# untitled.net
KiCad netlist of a schematic drawn in EAGLE
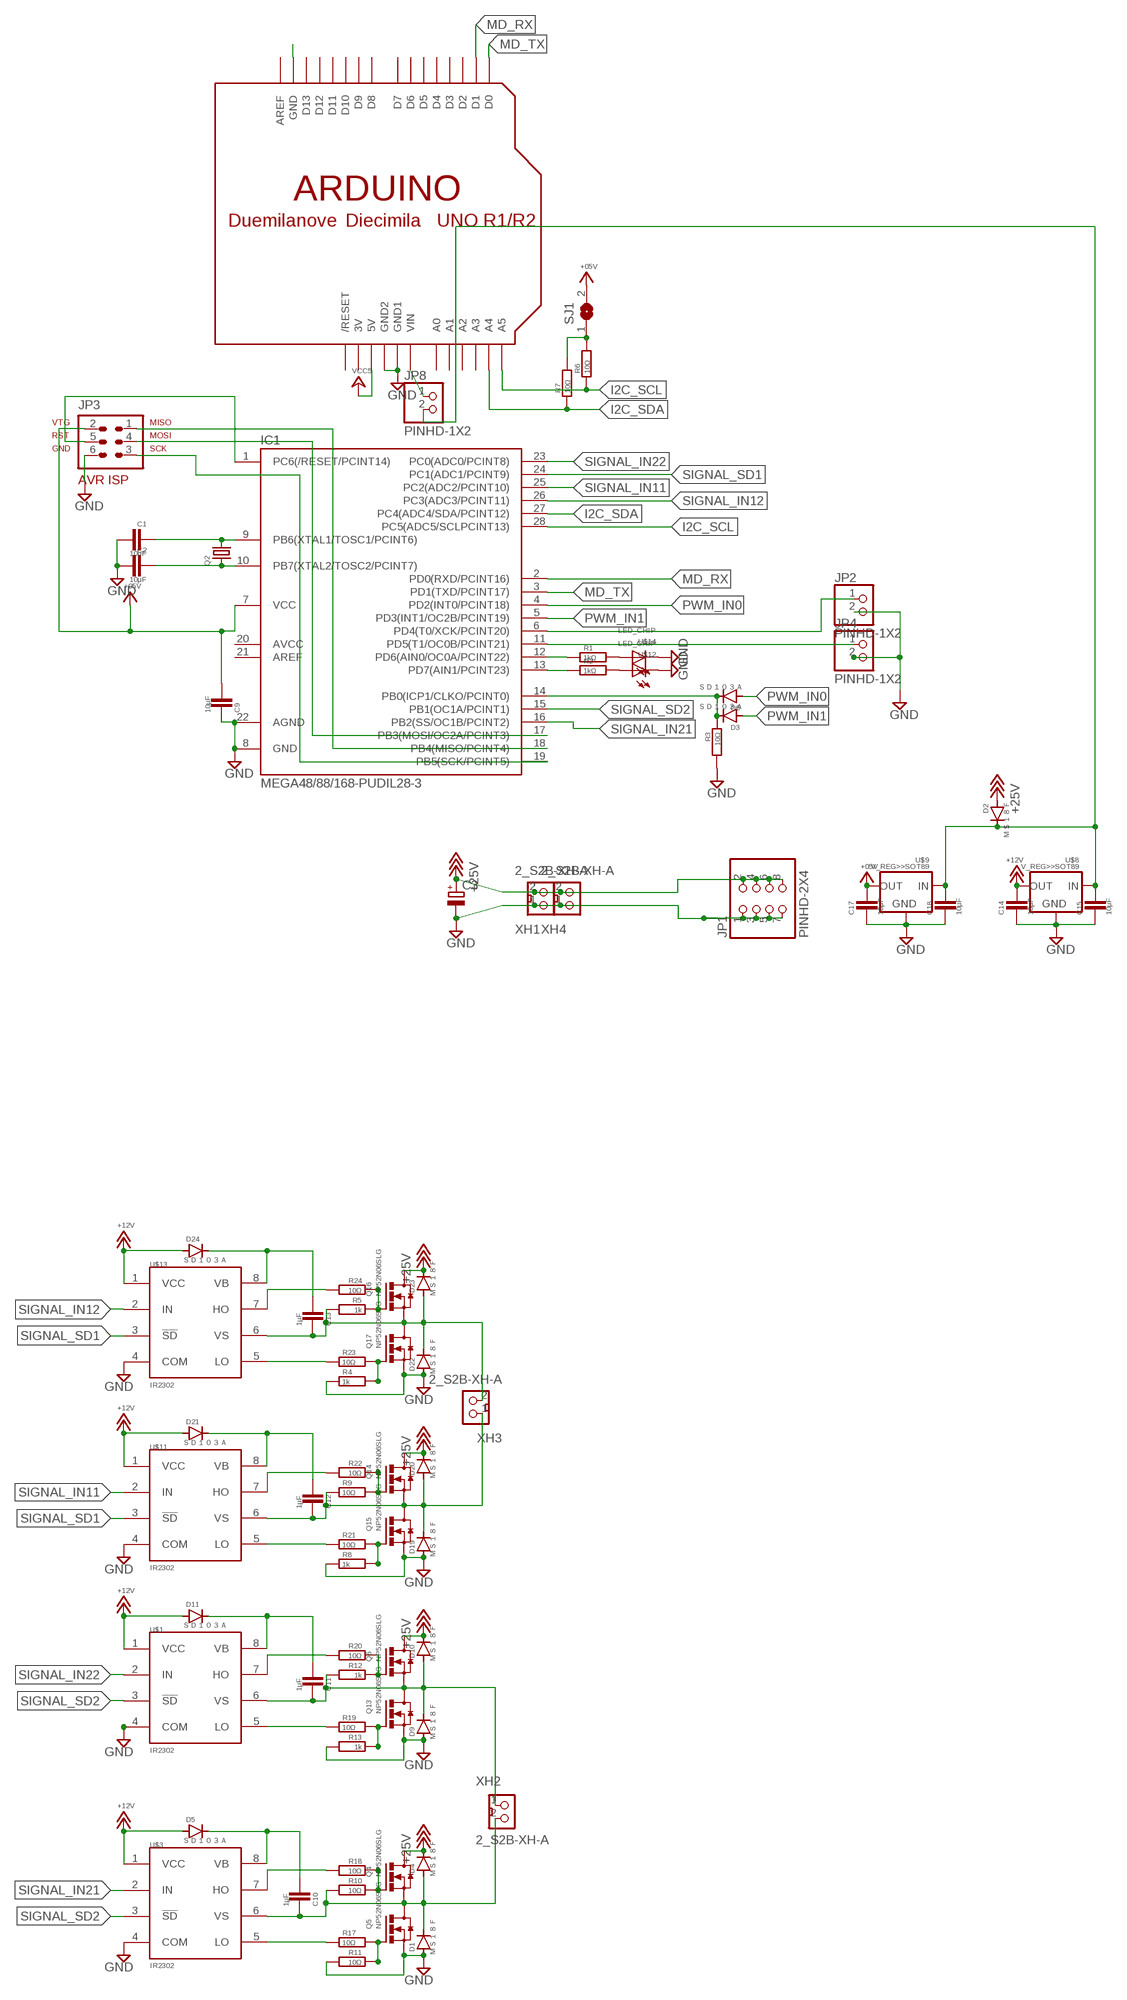
[diagram p0: schematic, sheet 1]

(export (version "E")
  (design (tool "Eeschema 10.0.6"))
  (components
    (comp (ref "C1")
      (value "10μF")
      (footprint "eagle-import:2012")
      (libsource (lib "eagle-import") (part "CAPACITOR{gt}{gt}2012"))
    )
    (comp (ref "C2")
      (value "10μF")
      (footprint "eagle-import:2012")
      (libsource (lib "eagle-import") (part "CAPACITOR{gt}{gt}2012"))
    )
    (comp (ref "C3")
      (value "CPOL-EUUD-6,3X8,8")
      (footprint "eagle-import:UD-6,3X5,8_NICHICON")
      (libsource (lib "eagle-import") (part "CPOL-EUUD-6,3X8,8"))
    )
    (comp (ref "C9")
      (value "10μF")
      (footprint "eagle-import:2012")
      (libsource (lib "eagle-import") (part "CAPACITOR{gt}{gt}2012"))
    )
    (comp (ref "C10")
      (value "1μF")
      (footprint "eagle-import:2012")
      (libsource (lib "eagle-import") (part "CAPACITOR{gt}{gt}2012"))
    )
    (comp (ref "C11")
      (value "1μF")
      (footprint "eagle-import:2012")
      (libsource (lib "eagle-import") (part "CAPACITOR{gt}{gt}2012"))
    )
    (comp (ref "C12")
      (value "1μF")
      (footprint "eagle-import:2012")
      (libsource (lib "eagle-import") (part "CAPACITOR{gt}{gt}2012"))
    )
    (comp (ref "C13")
      (value "1μF")
      (footprint "eagle-import:2012")
      (libsource (lib "eagle-import") (part "CAPACITOR{gt}{gt}2012"))
    )
    (comp (ref "C14")
      (value "10μF")
      (footprint "eagle-import:2012")
      (libsource (lib "eagle-import") (part "CAPACITOR{gt}{gt}2012"))
    )
    (comp (ref "C15")
      (value "10μF")
      (footprint "eagle-import:2012")
      (libsource (lib "eagle-import") (part "CAPACITOR{gt}{gt}2012"))
    )
    (comp (ref "C17")
      (value "10μF")
      (footprint "eagle-import:2012")
      (libsource (lib "eagle-import") (part "CAPACITOR{gt}{gt}2012"))
    )
    (comp (ref "C18")
      (value "10μF")
      (footprint "eagle-import:2012")
      (libsource (lib "eagle-import") (part "CAPACITOR{gt}{gt}2012"))
    )
    (comp (ref "D1")
      (value "ＭＳ１８Ｆ")
      (footprint "eagle-import:MS18F")
      (libsource (lib "eagle-import") (part "DIODE{gt}{gt}MS18F"))
    )
    (comp (ref "D2")
      (value "ＭＳ１８Ｆ")
      (footprint "eagle-import:MS18F")
      (libsource (lib "eagle-import") (part "DIODE{gt}{gt}MS18F"))
    )
    (comp (ref "D3")
      (value "ＳＤ１０３Ａ")
      (footprint "eagle-import:SOD123")
      (libsource (lib "eagle-import") (part "DIODE{gt}{gt}SOD123"))
    )
    (comp (ref "D4")
      (value "ＭＳ１８Ｆ")
      (footprint "eagle-import:MS18F")
      (libsource (lib "eagle-import") (part "DIODE{gt}{gt}MS18F"))
    )
    (comp (ref "D5")
      (value "ＳＤ１０３Ａ")
      (footprint "eagle-import:SOD123")
      (libsource (lib "eagle-import") (part "DIODE{gt}{gt}SOD123"))
    )
    (comp (ref "D6")
      (value "ＳＤ１０３Ａ")
      (footprint "eagle-import:SOD123")
      (libsource (lib "eagle-import") (part "DIODE{gt}{gt}SOD123"))
    )
    (comp (ref "D9")
      (value "ＭＳ１８Ｆ")
      (footprint "eagle-import:MS18F")
      (libsource (lib "eagle-import") (part "DIODE{gt}{gt}MS18F"))
    )
    (comp (ref "D10")
      (value "ＭＳ１８Ｆ")
      (footprint "eagle-import:MS18F")
      (libsource (lib "eagle-import") (part "DIODE{gt}{gt}MS18F"))
    )
    (comp (ref "D11")
      (value "ＳＤ１０３Ａ")
      (footprint "eagle-import:SOD123")
      (libsource (lib "eagle-import") (part "DIODE{gt}{gt}SOD123"))
    )
    (comp (ref "D19")
      (value "ＭＳ１８Ｆ")
      (footprint "eagle-import:MS18F")
      (libsource (lib "eagle-import") (part "DIODE{gt}{gt}MS18F"))
    )
    (comp (ref "D20")
      (value "ＭＳ１８Ｆ")
      (footprint "eagle-import:MS18F")
      (libsource (lib "eagle-import") (part "DIODE{gt}{gt}MS18F"))
    )
    (comp (ref "D21")
      (value "ＳＤ１０３Ａ")
      (footprint "eagle-import:SOD123")
      (libsource (lib "eagle-import") (part "DIODE{gt}{gt}SOD123"))
    )
    (comp (ref "D22")
      (value "ＭＳ１８Ｆ")
      (footprint "eagle-import:MS18F")
      (libsource (lib "eagle-import") (part "DIODE{gt}{gt}MS18F"))
    )
    (comp (ref "D23")
      (value "ＭＳ１８Ｆ")
      (footprint "eagle-import:MS18F")
      (libsource (lib "eagle-import") (part "DIODE{gt}{gt}MS18F"))
    )
    (comp (ref "D24")
      (value "ＳＤ１０３Ａ")
      (footprint "eagle-import:SOD123")
      (libsource (lib "eagle-import") (part "DIODE{gt}{gt}SOD123"))
    )
    (comp (ref "IC1")
      (value "MEGA48/88/168-PUDIL28-3")
      (footprint "eagle-import:DIL28-3")
      (libsource (lib "eagle-import") (part "MEGA48/88/168-PUDIL28-3"))
    )
    (comp (ref "JP1")
      (value "PINHD-2X4")
      (footprint "eagle-import:2X04")
      (libsource (lib "eagle-import") (part "PINHD-2X4"))
    )
    (comp (ref "JP2")
      (value "PINHD-1X2")
      (footprint "eagle-import:1X02")
      (libsource (lib "eagle-import") (part "PINHD-1X2"))
    )
    (comp (ref "JP3")
      (value "AVR-ISP-6")
      (footprint "eagle-import:AVR-ISP-6")
      (libsource (lib "eagle-import") (part "AVR-ISP-6"))
    )
    (comp (ref "JP4")
      (value "PINHD-1X2")
      (footprint "eagle-import:1X02")
      (libsource (lib "eagle-import") (part "PINHD-1X2"))
    )
    (comp (ref "JP8")
      (value "PINHD-1X2")
      (footprint "eagle-import:1X02")
      (libsource (lib "eagle-import") (part "PINHD-1X2"))
    )
    (comp (ref "Q2")
      (value "CRYSTALHC49UP")
      (footprint "eagle-import:HC49UP")
      (libsource (lib "eagle-import") (part "CRYSTALHC49UP"))
    )
    (comp (ref "Q4")
      (value "NP52N06SLG")
      (footprint "eagle-import:TO252")
      (libsource (lib "eagle-import") (part "MOSFET_N{gt}{gt}TO252"))
    )
    (comp (ref "Q5")
      (value "NP52N06SLG")
      (footprint "eagle-import:TO252")
      (libsource (lib "eagle-import") (part "MOSFET_N{gt}{gt}TO252"))
    )
    (comp (ref "Q6")
      (value "NP52N06SLG")
      (footprint "eagle-import:TO252")
      (libsource (lib "eagle-import") (part "MOSFET_N{gt}{gt}TO252"))
    )
    (comp (ref "Q13")
      (value "NP52N06SLG")
      (footprint "eagle-import:TO252")
      (libsource (lib "eagle-import") (part "MOSFET_N{gt}{gt}TO252"))
    )
    (comp (ref "Q14")
      (value "NP52N06SLG")
      (footprint "eagle-import:TO252")
      (libsource (lib "eagle-import") (part "MOSFET_N{gt}{gt}TO252"))
    )
    (comp (ref "Q15")
      (value "NP52N06SLG")
      (footprint "eagle-import:TO252")
      (libsource (lib "eagle-import") (part "MOSFET_N{gt}{gt}TO252"))
    )
    (comp (ref "Q16")
      (value "NP52N06SLG")
      (footprint "eagle-import:TO252")
      (libsource (lib "eagle-import") (part "MOSFET_N{gt}{gt}TO252"))
    )
    (comp (ref "Q17")
      (value "NP52N06SLG")
      (footprint "eagle-import:TO252")
      (libsource (lib "eagle-import") (part "MOSFET_N{gt}{gt}TO252"))
    )
    (comp (ref "R1")
      (value "1kΩ")
      (footprint "eagle-import:2012")
      (libsource (lib "eagle-import") (part "REGISTER{gt}{gt}2012"))
    )
    (comp (ref "R2")
      (value "1kΩ")
      (footprint "eagle-import:2012")
      (libsource (lib "eagle-import") (part "REGISTER{gt}{gt}2012"))
    )
    (comp (ref "R3")
      (value "10Ω")
      (footprint "eagle-import:2012")
      (libsource (lib "eagle-import") (part "REGISTER{gt}{gt}2012"))
    )
    (comp (ref "R4")
      (value "1k")
      (footprint "eagle-import:2012")
      (libsource (lib "eagle-import") (part "REGISTER{gt}{gt}2012"))
    )
    (comp (ref "R5")
      (value "1k")
      (footprint "eagle-import:2012")
      (libsource (lib "eagle-import") (part "REGISTER{gt}{gt}2012"))
    )
    (comp (ref "R6")
      (value "10Ω")
      (footprint "eagle-import:2012")
      (libsource (lib "eagle-import") (part "REGISTER{gt}{gt}2012"))
    )
    (comp (ref "R7")
      (value "10Ω")
      (footprint "eagle-import:2012")
      (libsource (lib "eagle-import") (part "REGISTER{gt}{gt}2012"))
    )
    (comp (ref "R8")
      (value "1k")
      (footprint "eagle-import:2012")
      (libsource (lib "eagle-import") (part "REGISTER{gt}{gt}2012"))
    )
    (comp (ref "R9")
      (value "10Ω")
      (footprint "eagle-import:2012")
      (libsource (lib "eagle-import") (part "REGISTER{gt}{gt}2012"))
    )
    (comp (ref "R10")
      (value "10Ω")
      (footprint "eagle-import:2012")
      (libsource (lib "eagle-import") (part "REGISTER{gt}{gt}2012"))
    )
    (comp (ref "R11")
      (value "10Ω")
      (footprint "eagle-import:2012")
      (libsource (lib "eagle-import") (part "REGISTER{gt}{gt}2012"))
    )
    (comp (ref "R12")
      (value "1k")
      (footprint "eagle-import:2012")
      (libsource (lib "eagle-import") (part "REGISTER{gt}{gt}2012"))
    )
    (comp (ref "R13")
      (value "1k")
      (footprint "eagle-import:2012")
      (libsource (lib "eagle-import") (part "REGISTER{gt}{gt}2012"))
    )
    (comp (ref "R17")
      (value "10Ω")
      (footprint "eagle-import:2012")
      (libsource (lib "eagle-import") (part "REGISTER{gt}{gt}2012"))
    )
    (comp (ref "R18")
      (value "10Ω")
      (footprint "eagle-import:2012")
      (libsource (lib "eagle-import") (part "REGISTER{gt}{gt}2012"))
    )
    (comp (ref "R19")
      (value "10Ω")
      (footprint "eagle-import:2012")
      (libsource (lib "eagle-import") (part "REGISTER{gt}{gt}2012"))
    )
    (comp (ref "R20")
      (value "10Ω")
      (footprint "eagle-import:2012")
      (libsource (lib "eagle-import") (part "REGISTER{gt}{gt}2012"))
    )
    (comp (ref "R21")
      (value "10Ω")
      (footprint "eagle-import:2012")
      (libsource (lib "eagle-import") (part "REGISTER{gt}{gt}2012"))
    )
    (comp (ref "R22")
      (value "10Ω")
      (footprint "eagle-import:2012")
      (libsource (lib "eagle-import") (part "REGISTER{gt}{gt}2012"))
    )
    (comp (ref "R23")
      (value "10Ω")
      (footprint "eagle-import:2012")
      (libsource (lib "eagle-import") (part "REGISTER{gt}{gt}2012"))
    )
    (comp (ref "R24")
      (value "10Ω")
      (footprint "eagle-import:2012")
      (libsource (lib "eagle-import") (part "REGISTER{gt}{gt}2012"))
    )
    (comp (ref "SJ1") (value "SJ") (footprint "eagle-import:SJ") (libsource (lib "eagle-import") (part "SJ")))
    (comp (ref "U$1")
      (value "IR2302")
      (footprint "eagle-import:DIL08")
      (libsource (lib "eagle-import") (part "IR2302IR2302"))
    )
    (comp (ref "U$2")
      (value "ARDUINO-NOHOLE")
      (footprint "eagle-import:ARDUINO-NOHOLE")
      (libsource (lib "eagle-import") (part "ARDUINO-NOHOLE"))
    )
    (comp (ref "U$3")
      (value "IR2302")
      (footprint "eagle-import:DIL08")
      (libsource (lib "eagle-import") (part "IR2302IR2302"))
    )
    (comp (ref "U$8")
      (value "V_REG>>SOT89")
      (footprint "eagle-import:SOT89")
      (libsource (lib "eagle-import") (part "V_REG{gt}{gt}SOT89"))
    )
    (comp (ref "U$9")
      (value "V_REG>>SOT89")
      (footprint "eagle-import:SOT89")
      (libsource (lib "eagle-import") (part "V_REG{gt}{gt}SOT89"))
    )
    (comp (ref "U$11")
      (value "IR2302")
      (footprint "eagle-import:DIL08")
      (libsource (lib "eagle-import") (part "IR2302IR2302"))
    )
    (comp (ref "U$12")
      (value "LED_CHIP")
      (footprint "eagle-import:2012")
      (libsource (lib "eagle-import") (part "LED_CHIP"))
    )
    (comp (ref "U$13")
      (value "IR2302")
      (footprint "eagle-import:DIL08")
      (libsource (lib "eagle-import") (part "IR2302IR2302"))
    )
    (comp (ref "U$14")
      (value "LED_CHIP")
      (footprint "eagle-import:2012")
      (libsource (lib "eagle-import") (part "LED_CHIP"))
    )
    (comp (ref "XH1")
      (value "2_S2B-XH-A")
      (footprint "eagle-import:S2B-XH-A")
      (libsource (lib "eagle-import") (part "2_S2B-XH-A"))
    )
    (comp (ref "XH2")
      (value "2_S2B-XH-A")
      (footprint "eagle-import:S2B-XH-A")
      (libsource (lib "eagle-import") (part "2_S2B-XH-A"))
    )
    (comp (ref "XH3")
      (value "2_S2B-XH-A")
      (footprint "eagle-import:S2B-XH-A")
      (libsource (lib "eagle-import") (part "2_S2B-XH-A"))
    )
    (comp (ref "XH4")
      (value "2_S2B-XH-A")
      (footprint "eagle-import:S2B-XH-A")
      (libsource (lib "eagle-import") (part "2_S2B-XH-A"))
    )
  )
  (nets
    (net (code "1") (name "+05V") (class "Default")
      (node (ref "C17") (pin "1") (pinfunction "1_1") (pintype "passive"))
      (node (ref "C9") (pin "1") (pinfunction "1_1") (pintype "passive"))
      (node (ref "IC1") (pin "7") (pinfunction "VCC_7") (pintype "power_in"))
      (node (ref "JP3") (pin "2") (pinfunction "2_2") (pintype "passive"))
      (node (ref "SJ1") (pin "2") (pinfunction "2_2") (pintype "passive"))
      (node (ref "U$9") (pin "1") (pinfunction "OUT_1") (pintype "passive"))
    )
    (net (code "2") (name "+12V") (class "Default")
      (node (ref "C14") (pin "1") (pinfunction "1_1") (pintype "passive"))
      (node (ref "D11") (pin "A") (pinfunction "A_A") (pintype "passive"))
      (node (ref "D21") (pin "A") (pinfunction "A_A") (pintype "passive"))
      (node (ref "D24") (pin "A") (pinfunction "A_A") (pintype "passive"))
      (node (ref "D5") (pin "A") (pinfunction "A_A") (pintype "passive"))
      (node (ref "U$1") (pin "1") (pinfunction "VCC_1") (pintype "bidirectional"))
      (node (ref "U$11") (pin "1") (pinfunction "VCC_1") (pintype "bidirectional"))
      (node (ref "U$13") (pin "1") (pinfunction "VCC_1") (pintype "bidirectional"))
      (node (ref "U$3") (pin "1") (pinfunction "VCC_1") (pintype "bidirectional"))
      (node (ref "U$8") (pin "1") (pinfunction "OUT_1") (pintype "passive"))
    )
    (net (code "3") (name "+25V") (class "Default")
      (node (ref "C3") (pin "+") (pinfunction "+_+") (pintype "passive"))
      (node (ref "D10") (pin "P$2") (pinfunction "C_P$2") (pintype "passive"))
      (node (ref "D2") (pin "P$1") (pinfunction "A_P$1") (pintype "passive"))
      (node (ref "D20") (pin "P$2") (pinfunction "C_P$2") (pintype "passive"))
      (node (ref "D23") (pin "P$2") (pinfunction "C_P$2") (pintype "passive"))
      (node (ref "D4") (pin "P$2") (pinfunction "C_P$2") (pintype "passive"))
      (node (ref "JP1") (pin "2") (pinfunction "2_2") (pintype "passive"))
      (node (ref "JP1") (pin "4") (pinfunction "4_4") (pintype "passive"))
      (node (ref "JP1") (pin "6") (pinfunction "6_6") (pintype "passive"))
      (node (ref "JP1") (pin "8") (pinfunction "8_8") (pintype "passive"))
      (node (ref "Q14") (pin "3") (pinfunction "D_3") (pintype "passive"))
      (node (ref "Q16") (pin "3") (pinfunction "D_3") (pintype "passive"))
      (node (ref "Q4") (pin "3") (pinfunction "D_3") (pintype "passive"))
      (node (ref "Q6") (pin "3") (pinfunction "D_3") (pintype "passive"))
      (node (ref "XH1") (pin "2") (pinfunction "2_2") (pintype "passive"))
      (node (ref "XH4") (pin "2") (pinfunction "2_2") (pintype "passive"))
    )
    (net (code "4") (name "/3V") (class "Default")
      (node (ref "U$2") (pin "3V") (pinfunction "3V_3V") (pintype "power_in"))
    )
    (net (code "5") (name "GND") (class "Default")
      (node (ref "C1") (pin "1") (pinfunction "1_1") (pintype "passive"))
      (node (ref "C14") (pin "2") (pinfunction "2_2") (pintype "passive"))
      (node (ref "C15") (pin "2") (pinfunction "2_2") (pintype "passive"))
      (node (ref "C17") (pin "2") (pinfunction "2_2") (pintype "passive"))
      (node (ref "C18") (pin "2") (pinfunction "2_2") (pintype "passive"))
      (node (ref "C2") (pin "1") (pinfunction "1_1") (pintype "passive"))
      (node (ref "C3") (pin "-") (pinfunction "-_-") (pintype "passive"))
      (node (ref "C9") (pin "2") (pinfunction "2_2") (pintype "passive"))
      (node (ref "D1") (pin "P$1") (pinfunction "A_P$1") (pintype "passive"))
      (node (ref "D19") (pin "P$1") (pinfunction "A_P$1") (pintype "passive"))
      (node (ref "D22") (pin "P$1") (pinfunction "A_P$1") (pintype "passive"))
      (node (ref "D9") (pin "P$1") (pinfunction "A_P$1") (pintype "passive"))
      (node (ref "IC1") (pin "22") (pinfunction "AGND_22") (pintype "power_in"))
      (node (ref "IC1") (pin "8") (pinfunction "GND_8") (pintype "power_in"))
      (node (ref "JP1") (pin "1") (pinfunction "1_1") (pintype "passive"))
      (node (ref "JP1") (pin "3") (pinfunction "3_3") (pintype "passive"))
      (node (ref "JP1") (pin "5") (pinfunction "5_5") (pintype "passive"))
      (node (ref "JP1") (pin "7") (pinfunction "7_7") (pintype "passive"))
      (node (ref "JP2") (pin "2") (pinfunction "2_2") (pintype "passive"))
      (node (ref "JP3") (pin "6") (pinfunction "6_6") (pintype "passive"))
      (node (ref "JP4") (pin "2") (pinfunction "2_2") (pintype "passive"))
      (node (ref "Q13") (pin "2") (pinfunction "S_2") (pintype "passive"))
      (node (ref "Q15") (pin "2") (pinfunction "S_2") (pintype "passive"))
      (node (ref "Q17") (pin "2") (pinfunction "S_2") (pintype "passive"))
      (node (ref "Q5") (pin "2") (pinfunction "S_2") (pintype "passive"))
      (node (ref "R11") (pin "2") (pinfunction "2_2") (pintype "passive"))
      (node (ref "R13") (pin "2") (pinfunction "2_2") (pintype "passive"))
      (node (ref "R3") (pin "2") (pinfunction "2_2") (pintype "passive"))
      (node (ref "R4") (pin "1") (pinfunction "1_1") (pintype "passive"))
      (node (ref "R8") (pin "1") (pinfunction "1_1") (pintype "passive"))
      (node (ref "U$1") (pin "4") (pinfunction "COM_4") (pintype "bidirectional"))
      (node (ref "U$11") (pin "4") (pinfunction "COM_4") (pintype "bidirectional"))
      (node (ref "U$12") (pin "P$2") (pinfunction "C_P$2") (pintype "passive"))
      (node (ref "U$13") (pin "4") (pinfunction "COM_4") (pintype "bidirectional"))
      (node (ref "U$14") (pin "P$2") (pinfunction "C_P$2") (pintype "passive"))
      (node (ref "U$2") (pin "GND1") (pinfunction "GND1_GND1") (pintype "power_in"))
      (node (ref "U$2") (pin "GND2") (pinfunction "GND2_GND2") (pintype "power_in"))
      (node (ref "U$3") (pin "4") (pinfunction "COM_4") (pintype "bidirectional"))
      (node (ref "U$8") (pin "2") (pinfunction "GND_2") (pintype "input"))
      (node (ref "U$8") (pin "2.1") (pinfunction "GND_2.1") (pintype "input"))
      (node (ref "U$9") (pin "2") (pinfunction "GND_2") (pintype "input"))
      (node (ref "U$9") (pin "2.1") (pinfunction "GND_2.1") (pintype "input"))
      (node (ref "XH1") (pin "1") (pinfunction "1_1") (pintype "passive"))
      (node (ref "XH4") (pin "1") (pinfunction "1_1") (pintype "passive"))
    )
    (net (code "6") (name "I2C_SCL") (class "Default")
      (node (ref "IC1") (pin "28") (pinfunction "PC5(ADC5/SCLPCINT13)_28") (pintype "bidirectional"))
      (node (ref "R6") (pin "1") (pinfunction "1_1") (pintype "passive"))
      (node (ref "U$2") (pin "A5") (pinfunction "A5_A5") (pintype "bidirectional"))
    )
    (net (code "7") (name "I2C_SDA") (class "Default")
      (node (ref "IC1") (pin "27") (pinfunction "PC4(ADC4/SDA/PCINT12)_27") (pintype "bidirectional"))
      (node (ref "R7") (pin "1") (pinfunction "1_1") (pintype "passive"))
      (node (ref "U$2") (pin "A4") (pinfunction "A4_A4") (pintype "bidirectional"))
    )
    (net (code "8") (name "MD_RX") (class "Default")
      (node (ref "IC1") (pin "2") (pinfunction "PD0(RXD/PCINT16)_2") (pintype "bidirectional"))
      (node (ref "U$2") (pin "D1") (pinfunction "D1_D1") (pintype "bidirectional"))
    )
    (net (code "9") (name "MD_TX") (class "Default")
      (node (ref "IC1") (pin "3") (pinfunction "PD1(TXD/PCINT17)_3") (pintype "bidirectional"))
      (node (ref "U$2") (pin "D0") (pinfunction "D0_D0") (pintype "bidirectional"))
    )
    (net (code "10") (name "Net-(D1-C)") (class "Default")
      (node (ref "C10") (pin "2") (pinfunction "2_2") (pintype "passive"))
      (node (ref "D1") (pin "P$2") (pinfunction "C_P$2") (pintype "passive"))
      (node (ref "D4") (pin "P$1") (pinfunction "A_P$1") (pintype "passive"))
      (node (ref "Q4") (pin "2") (pinfunction "S_2") (pintype "passive"))
      (node (ref "Q5") (pin "3") (pinfunction "D_3") (pintype "passive"))
      (node (ref "R10") (pin "2") (pinfunction "2_2") (pintype "passive"))
      (node (ref "U$3") (pin "6") (pinfunction "VS_6") (pintype "bidirectional"))
      (node (ref "XH2") (pin "2") (pinfunction "2_2") (pintype "passive"))
    )
    (net (code "11") (name "Net-(D2-C)") (class "Default")
      (node (ref "C15") (pin "1") (pinfunction "1_1") (pintype "passive"))
      (node (ref "C18") (pin "1") (pinfunction "1_1") (pintype "passive"))
      (node (ref "D2") (pin "P$2") (pinfunction "C_P$2") (pintype "passive"))
      (node (ref "JP8") (pin "2") (pinfunction "2_2") (pintype "passive"))
      (node (ref "U$8") (pin "3") (pinfunction "IN_3") (pintype "input"))
      (node (ref "U$9") (pin "3") (pinfunction "IN_3") (pintype "input"))
    )
    (net (code "12") (name "Net-(D10-A)") (class "Default")
      (node (ref "C11") (pin "2") (pinfunction "2_2") (pintype "passive"))
      (node (ref "D10") (pin "P$1") (pinfunction "A_P$1") (pintype "passive"))
      (node (ref "D9") (pin "P$2") (pinfunction "C_P$2") (pintype "passive"))
      (node (ref "Q13") (pin "3") (pinfunction "D_3") (pintype "passive"))
      (node (ref "Q6") (pin "2") (pinfunction "S_2") (pintype "passive"))
      (node (ref "R12") (pin "2") (pinfunction "2_2") (pintype "passive"))
      (node (ref "U$1") (pin "6") (pinfunction "VS_6") (pintype "bidirectional"))
      (node (ref "XH2") (pin "1") (pinfunction "1_1") (pintype "passive"))
    )
    (net (code "13") (name "Net-(D19-C)") (class "Default")
      (node (ref "C12") (pin "2") (pinfunction "2_2") (pintype "passive"))
      (node (ref "D19") (pin "P$2") (pinfunction "C_P$2") (pintype "passive"))
      (node (ref "D20") (pin "P$1") (pinfunction "A_P$1") (pintype "passive"))
      (node (ref "Q14") (pin "2") (pinfunction "S_2") (pintype "passive"))
      (node (ref "Q15") (pin "3") (pinfunction "D_3") (pintype "passive"))
      (node (ref "R9") (pin "1") (pinfunction "1_1") (pintype "passive"))
      (node (ref "U$11") (pin "6") (pinfunction "VS_6") (pintype "bidirectional"))
      (node (ref "XH3") (pin "1") (pinfunction "1_1") (pintype "passive"))
    )
    (net (code "14") (name "Net-(D22-C)") (class "Default")
      (node (ref "C13") (pin "2") (pinfunction "2_2") (pintype "passive"))
      (node (ref "D22") (pin "P$2") (pinfunction "C_P$2") (pintype "passive"))
      (node (ref "D23") (pin "P$1") (pinfunction "A_P$1") (pintype "passive"))
      (node (ref "Q16") (pin "2") (pinfunction "S_2") (pintype "passive"))
      (node (ref "Q17") (pin "3") (pinfunction "D_3") (pintype "passive"))
      (node (ref "R5") (pin "2") (pinfunction "2_2") (pintype "passive"))
      (node (ref "U$13") (pin "6") (pinfunction "VS_6") (pintype "bidirectional"))
      (node (ref "XH3") (pin "2") (pinfunction "2_2") (pintype "passive"))
    )
    (net (code "15") (name "Net-(IC1-PB0(ICP1{slash}CLKO{slash}PCINT0))") (class "Default")
      (node (ref "D3") (pin "C") (pinfunction "C_C") (pintype "passive"))
      (node (ref "D6") (pin "C") (pinfunction "C_C") (pintype "passive"))
      (node (ref "IC1") (pin "14") (pinfunction "PB0(ICP1/CLKO/PCINT0)_14") (pintype "bidirectional"))
      (node (ref "R3") (pin "1") (pinfunction "1_1") (pintype "passive"))
    )
    (net (code "16") (name "Net-(IC1-PB3(MOSI{slash}OC2A{slash}PCINT3))") (class "Default")
      (node (ref "IC1") (pin "17") (pinfunction "PB3(MOSI/OC2A/PCINT3)_17") (pintype "bidirectional"))
      (node (ref "JP3") (pin "4") (pinfunction "4_4") (pintype "passive"))
    )
    (net (code "17") (name "Net-(IC1-PB4(MISO{slash}PCINT4))") (class "Default")
      (node (ref "IC1") (pin "18") (pinfunction "PB4(MISO/PCINT4)_18") (pintype "bidirectional"))
      (node (ref "JP3") (pin "1") (pinfunction "1_1") (pintype "passive"))
    )
    (net (code "18") (name "Net-(IC1-PB5(SCK{slash}PCINT5))") (class "Default")
      (node (ref "IC1") (pin "19") (pinfunction "PB5(SCK/PCINT5)_19") (pintype "bidirectional"))
      (node (ref "JP3") (pin "3") (pinfunction "3_3") (pintype "passive"))
    )
    (net (code "19") (name "Net-(IC1-PB6(XTAL1{slash}TOSC1{slash}PCINT6))") (class "Default")
      (node (ref "C1") (pin "2") (pinfunction "2_2") (pintype "passive"))
      (node (ref "IC1") (pin "9") (pinfunction "PB6(XTAL1/TOSC1/PCINT6)_9") (pintype "bidirectional"))
      (node (ref "Q2") (pin "2") (pinfunction "2_2") (pintype "passive"))
    )
    (net (code "20") (name "Net-(IC1-PB7(XTAL2{slash}TOSC2{slash}PCINT7))") (class "Default")
      (node (ref "C2") (pin "2") (pinfunction "2_2") (pintype "passive"))
      (node (ref "IC1") (pin "10") (pinfunction "PB7(XTAL2/TOSC2/PCINT7)_10") (pintype "bidirectional"))
      (node (ref "Q2") (pin "1") (pinfunction "1_1") (pintype "passive"))
    )
    (net (code "21") (name "Net-(IC1-PC6({slash}RESET{slash}PCINT14))") (class "Default")
      (node (ref "IC1") (pin "1") (pinfunction "PC6(/RESET/PCINT14)_1") (pintype "bidirectional"))
      (node (ref "JP3") (pin "5") (pinfunction "5_5") (pintype "passive"))
    )
    (net (code "22") (name "Net-(IC1-PD4(T0{slash}XCK{slash}PCINT20))") (class "Default")
      (node (ref "IC1") (pin "6") (pinfunction "PD4(T0/XCK/PCINT20)_6") (pintype "bidirectional"))
      (node (ref "JP2") (pin "1") (pinfunction "1_1") (pintype "passive"))
    )
    (net (code "23") (name "Net-(IC1-PD5(T1{slash}OC0B{slash}PCINT21))") (class "Default")
      (node (ref "IC1") (pin "11") (pinfunction "PD5(T1/OC0B/PCINT21)_11") (pintype "bidirectional"))
      (node (ref "JP4") (pin "1") (pinfunction "1_1") (pintype "passive"))
    )
    (net (code "24") (name "Net-(IC1-PD6(AIN0{slash}OC0A{slash}PCINT22))") (class "Default")
      (node (ref "IC1") (pin "12") (pinfunction "PD6(AIN0/OC0A/PCINT22)_12") (pintype "bidirectional"))
      (node (ref "R1") (pin "1") (pinfunction "1_1") (pintype "passive"))
    )
    (net (code "25") (name "Net-(IC1-PD7(AIN1{slash}PCINT23))") (class "Default")
      (node (ref "IC1") (pin "13") (pinfunction "PD7(AIN1/PCINT23)_13") (pintype "bidirectional"))
      (node (ref "R2") (pin "1") (pinfunction "1_1") (pintype "passive"))
    )
    (net (code "26") (name "Net-(JP8-Pad1)") (class "Default")
      (node (ref "JP8") (pin "1") (pinfunction "1_1") (pintype "passive"))
      (node (ref "U$2") (pin "VIN") (pinfunction "VIN_VIN") (pintype "power_in"))
    )
    (net (code "27") (name "Net-(Q4-G)") (class "Default")
      (node (ref "Q4") (pin "1") (pinfunction "G_1") (pintype "passive"))
      (node (ref "R10") (pin "1") (pinfunction "1_1") (pintype "passive"))
      (node (ref "R18") (pin "1") (pinfunction "1_1") (pintype "passive"))
    )
    (net (code "28") (name "Net-(Q5-G)") (class "Default")
      (node (ref "Q5") (pin "1") (pinfunction "G_1") (pintype "passive"))
      (node (ref "R11") (pin "1") (pinfunction "1_1") (pintype "passive"))
      (node (ref "R17") (pin "2") (pinfunction "2_2") (pintype "passive"))
    )
    (net (code "29") (name "Net-(Q6-G)") (class "Default")
      (node (ref "Q6") (pin "1") (pinfunction "G_1") (pintype "passive"))
      (node (ref "R12") (pin "1") (pinfunction "1_1") (pintype "passive"))
      (node (ref "R20") (pin "1") (pinfunction "1_1") (pintype "passive"))
    )
    (net (code "30") (name "Net-(Q13-G)") (class "Default")
      (node (ref "Q13") (pin "1") (pinfunction "G_1") (pintype "passive"))
      (node (ref "R13") (pin "1") (pinfunction "1_1") (pintype "passive"))
      (node (ref "R19") (pin "2") (pinfunction "2_2") (pintype "passive"))
    )
    (net (code "31") (name "Net-(Q14-G)") (class "Default")
      (node (ref "Q14") (pin "1") (pinfunction "G_1") (pintype "passive"))
      (node (ref "R22") (pin "1") (pinfunction "1_1") (pintype "passive"))
      (node (ref "R9") (pin "2") (pinfunction "2_2") (pintype "passive"))
    )
    (net (code "32") (name "Net-(Q15-G)") (class "Default")
      (node (ref "Q15") (pin "1") (pinfunction "G_1") (pintype "passive"))
      (node (ref "R21") (pin "2") (pinfunction "2_2") (pintype "passive"))
      (node (ref "R8") (pin "2") (pinfunction "2_2") (pintype "passive"))
    )
    (net (code "33") (name "Net-(Q16-G)") (class "Default")
      (node (ref "Q16") (pin "1") (pinfunction "G_1") (pintype "passive"))
      (node (ref "R24") (pin "1") (pinfunction "1_1") (pintype "passive"))
      (node (ref "R5") (pin "1") (pinfunction "1_1") (pintype "passive"))
    )
    (net (code "34") (name "Net-(Q17-G)") (class "Default")
      (node (ref "Q17") (pin "1") (pinfunction "G_1") (pintype "passive"))
      (node (ref "R23") (pin "2") (pinfunction "2_2") (pintype "passive"))
      (node (ref "R4") (pin "2") (pinfunction "2_2") (pintype "passive"))
    )
    (net (code "35") (name "Net-(R6-Pad2)") (class "Default")
      (node (ref "R6") (pin "2") (pinfunction "2_2") (pintype "passive"))
      (node (ref "R7") (pin "2") (pinfunction "2_2") (pintype "passive"))
      (node (ref "SJ1") (pin "1") (pinfunction "1_1") (pintype "passive"))
    )
    (net (code "36") (name "Net-(U$1-HO)") (class "Default")
      (node (ref "R20") (pin "2") (pinfunction "2_2") (pintype "passive"))
      (node (ref "U$1") (pin "7") (pinfunction "HO_7") (pintype "bidirectional"))
    )
    (net (code "37") (name "Net-(U$1-LO)") (class "Default")
      (node (ref "R19") (pin "1") (pinfunction "1_1") (pintype "passive"))
      (node (ref "U$1") (pin "5") (pinfunction "LO_5") (pintype "bidirectional"))
    )
    (net (code "38") (name "Net-(U$1-VB)") (class "Default")
      (node (ref "C11") (pin "1") (pinfunction "1_1") (pintype "passive"))
      (node (ref "D11") (pin "C") (pinfunction "C_C") (pintype "passive"))
      (node (ref "U$1") (pin "8") (pinfunction "VB_8") (pintype "bidirectional"))
    )
    (net (code "39") (name "Net-(U$3-HO)") (class "Default")
      (node (ref "R18") (pin "2") (pinfunction "2_2") (pintype "passive"))
      (node (ref "U$3") (pin "7") (pinfunction "HO_7") (pintype "bidirectional"))
    )
    (net (code "40") (name "Net-(U$3-LO)") (class "Default")
      (node (ref "R17") (pin "1") (pinfunction "1_1") (pintype "passive"))
      (node (ref "U$3") (pin "5") (pinfunction "LO_5") (pintype "bidirectional"))
    )
    (net (code "41") (name "Net-(U$3-VB)") (class "Default")
      (node (ref "C10") (pin "1") (pinfunction "1_1") (pintype "passive"))
      (node (ref "D5") (pin "C") (pinfunction "C_C") (pintype "passive"))
      (node (ref "U$3") (pin "8") (pinfunction "VB_8") (pintype "bidirectional"))
    )
    (net (code "42") (name "Net-(U$11-HO)") (class "Default")
      (node (ref "R22") (pin "2") (pinfunction "2_2") (pintype "passive"))
      (node (ref "U$11") (pin "7") (pinfunction "HO_7") (pintype "bidirectional"))
    )
    (net (code "43") (name "Net-(U$11-LO)") (class "Default")
      (node (ref "R21") (pin "1") (pinfunction "1_1") (pintype "passive"))
      (node (ref "U$11") (pin "5") (pinfunction "LO_5") (pintype "bidirectional"))
    )
    (net (code "44") (name "Net-(U$11-VB)") (class "Default")
      (node (ref "C12") (pin "1") (pinfunction "1_1") (pintype "passive"))
      (node (ref "D21") (pin "C") (pinfunction "C_C") (pintype "passive"))
      (node (ref "U$11") (pin "8") (pinfunction "VB_8") (pintype "bidirectional"))
    )
    (net (code "45") (name "Net-(U$12-A)") (class "Default")
      (node (ref "R2") (pin "2") (pinfunction "2_2") (pintype "passive"))
      (node (ref "U$12") (pin "P$1") (pinfunction "A_P$1") (pintype "passive"))
    )
    (net (code "46") (name "Net-(U$13-HO)") (class "Default")
      (node (ref "R24") (pin "2") (pinfunction "2_2") (pintype "passive"))
      (node (ref "U$13") (pin "7") (pinfunction "HO_7") (pintype "bidirectional"))
    )
    (net (code "47") (name "Net-(U$13-LO)") (class "Default")
      (node (ref "R23") (pin "1") (pinfunction "1_1") (pintype "passive"))
      (node (ref "U$13") (pin "5") (pinfunction "LO_5") (pintype "bidirectional"))
    )
    (net (code "48") (name "Net-(U$13-VB)") (class "Default")
      (node (ref "C13") (pin "1") (pinfunction "1_1") (pintype "passive"))
      (node (ref "D24") (pin "C") (pinfunction "C_C") (pintype "passive"))
      (node (ref "U$13") (pin "8") (pinfunction "VB_8") (pintype "bidirectional"))
    )
    (net (code "49") (name "Net-(U$14-A)") (class "Default")
      (node (ref "R1") (pin "2") (pinfunction "2_2") (pintype "passive"))
      (node (ref "U$14") (pin "P$1") (pinfunction "A_P$1") (pintype "passive"))
    )
    (net (code "50") (name "PWM_IN0") (class "Default")
      (node (ref "D6") (pin "A") (pinfunction "A_A") (pintype "passive"))
      (node (ref "IC1") (pin "4") (pinfunction "PD2(INT0/PCINT18)_4") (pintype "bidirectional"))
    )
    (net (code "51") (name "PWM_IN1") (class "Default")
      (node (ref "D3") (pin "A") (pinfunction "A_A") (pintype "passive"))
      (node (ref "IC1") (pin "5") (pinfunction "PD3(INT1/OC2B/PCINT19)_5") (pintype "bidirectional"))
    )
    (net (code "52") (name "SIGNAL_IN11") (class "Default")
      (node (ref "IC1") (pin "25") (pinfunction "PC2(ADC2/PCINT10)_25") (pintype "bidirectional"))
      (node (ref "U$11") (pin "2") (pinfunction "IN_2") (pintype "bidirectional"))
    )
    (net (code "53") (name "SIGNAL_IN12") (class "Default")
      (node (ref "IC1") (pin "26") (pinfunction "PC3(ADC3/PCINT11)_26") (pintype "bidirectional"))
      (node (ref "U$13") (pin "2") (pinfunction "IN_2") (pintype "bidirectional"))
    )
    (net (code "54") (name "SIGNAL_IN21") (class "Default")
      (node (ref "IC1") (pin "16") (pinfunction "PB2(SS/OC1B/PCINT2)_16") (pintype "bidirectional"))
      (node (ref "U$3") (pin "2") (pinfunction "IN_2") (pintype "bidirectional"))
    )
    (net (code "55") (name "SIGNAL_IN22") (class "Default")
      (node (ref "IC1") (pin "23") (pinfunction "PC0(ADC0/PCINT8)_23") (pintype "bidirectional"))
      (node (ref "U$1") (pin "2") (pinfunction "IN_2") (pintype "bidirectional"))
    )
    (net (code "56") (name "SIGNAL_SD1") (class "Default")
      (node (ref "IC1") (pin "24") (pinfunction "PC1(ADC1/PCINT9)_24") (pintype "bidirectional"))
      (node (ref "U$11") (pin "3") (pinfunction "~{SD}_3") (pintype "bidirectional"))
      (node (ref "U$13") (pin "3") (pinfunction "~{SD}_3") (pintype "bidirectional"))
    )
    (net (code "57") (name "SIGNAL_SD2") (class "Default")
      (node (ref "IC1") (pin "15") (pinfunction "PB1(OC1A/PCINT1)_15") (pintype "bidirectional"))
      (node (ref "U$1") (pin "3") (pinfunction "~{SD}_3") (pintype "bidirectional"))
      (node (ref "U$3") (pin "3") (pinfunction "~{SD}_3") (pintype "bidirectional"))
    )
    (net (code "58") (name "VCC5") (class "Default")
      (node (ref "U$2") (pin "5V") (pinfunction "5V_5V") (pintype "power_in"))
    )
    (net (code "59") (name "unconnected-(IC1-AREF-Pad21)") (class "Default")
      (node (ref "IC1") (pin "21") (pinfunction "AREF_21") (pintype "passive"))
    )
    (net (code "60") (name "unconnected-(IC1-AVCC-Pad20)") (class "Default")
      (node (ref "IC1") (pin "20") (pinfunction "AVCC_20") (pintype "passive"))
    )
    (net (code "61") (name "unconnected-(U$2-PadA0)") (class "Default")
      (node (ref "U$2") (pin "A0") (pinfunction "A0_A0") (pintype "bidirectional"))
    )
    (net (code "62") (name "unconnected-(U$2-PadA1)") (class "Default")
      (node (ref "U$2") (pin "A1") (pinfunction "A1_A1") (pintype "bidirectional"))
    )
    (net (code "63") (name "unconnected-(U$2-PadA2)") (class "Default")
      (node (ref "U$2") (pin "A2") (pinfunction "A2_A2") (pintype "bidirectional"))
    )
    (net (code "64") (name "unconnected-(U$2-PadA3)") (class "Default")
      (node (ref "U$2") (pin "A3") (pinfunction "A3_A3") (pintype "bidirectional"))
    )
    (net (code "65") (name "unconnected-(U$2-PadAREF)") (class "Default")
      (node (ref "U$2") (pin "AREF") (pinfunction "AREF_AREF") (pintype "bidirectional"))
    )
    (net (code "66") (name "unconnected-(U$2-PadD2)") (class "Default")
      (node (ref "U$2") (pin "D2") (pinfunction "D2_D2") (pintype "bidirectional"))
    )
    (net (code "67") (name "unconnected-(U$2-PadD3)") (class "Default")
      (node (ref "U$2") (pin "D3") (pinfunction "D3_D3") (pintype "bidirectional"))
    )
    (net (code "68") (name "unconnected-(U$2-PadD4)") (class "Default")
      (node (ref "U$2") (pin "D4") (pinfunction "D4_D4") (pintype "bidirectional"))
    )
    (net (code "69") (name "unconnected-(U$2-PadD5)") (class "Default")
      (node (ref "U$2") (pin "D5") (pinfunction "D5_D5") (pintype "bidirectional"))
    )
    (net (code "70") (name "unconnected-(U$2-PadD6)") (class "Default")
      (node (ref "U$2") (pin "D6") (pinfunction "D6_D6") (pintype "bidirectional"))
    )
    (net (code "71") (name "unconnected-(U$2-PadD7)") (class "Default")
      (node (ref "U$2") (pin "D7") (pinfunction "D7_D7") (pintype "bidirectional"))
    )
    (net (code "72") (name "unconnected-(U$2-PadD8)") (class "Default")
      (node (ref "U$2") (pin "D8") (pinfunction "D8_D8") (pintype "bidirectional"))
    )
    (net (code "73") (name "unconnected-(U$2-PadD9)") (class "Default")
      (node (ref "U$2") (pin "D9") (pinfunction "D9_D9") (pintype "bidirectional"))
    )
    (net (code "74") (name "unconnected-(U$2-PadD10)") (class "Default")
      (node (ref "U$2") (pin "D10") (pinfunction "D10_D10") (pintype "bidirectional"))
    )
    (net (code "75") (name "unconnected-(U$2-PadD11)") (class "Default")
      (node (ref "U$2") (pin "D11") (pinfunction "D11_D11") (pintype "bidirectional"))
    )
    (net (code "76") (name "unconnected-(U$2-PadD12)") (class "Default")
      (node (ref "U$2") (pin "D12") (pinfunction "D12_D12") (pintype "bidirectional"))
    )
    (net (code "77") (name "unconnected-(U$2-PadD13)") (class "Default")
      (node (ref "U$2") (pin "D13") (pinfunction "D13_D13") (pintype "bidirectional"))
    )
    (net (code "78") (name "unconnected-(U$2-PadGND)") (class "Default")
      (node (ref "U$2") (pin "GND") (pinfunction "GND_GND") (pintype "power_in"))
    )
    (net (code "79") (name "unconnected-(U$2-{slash}RESET-PadRESET)") (class "Default")
      (node (ref "U$2") (pin "RESET") (pinfunction "/RESET_RESET") (pintype "bidirectional"))
    )
  )
)
